# hv_relay_array.net
KiCad netlist of a schematic drawn in EAGLE
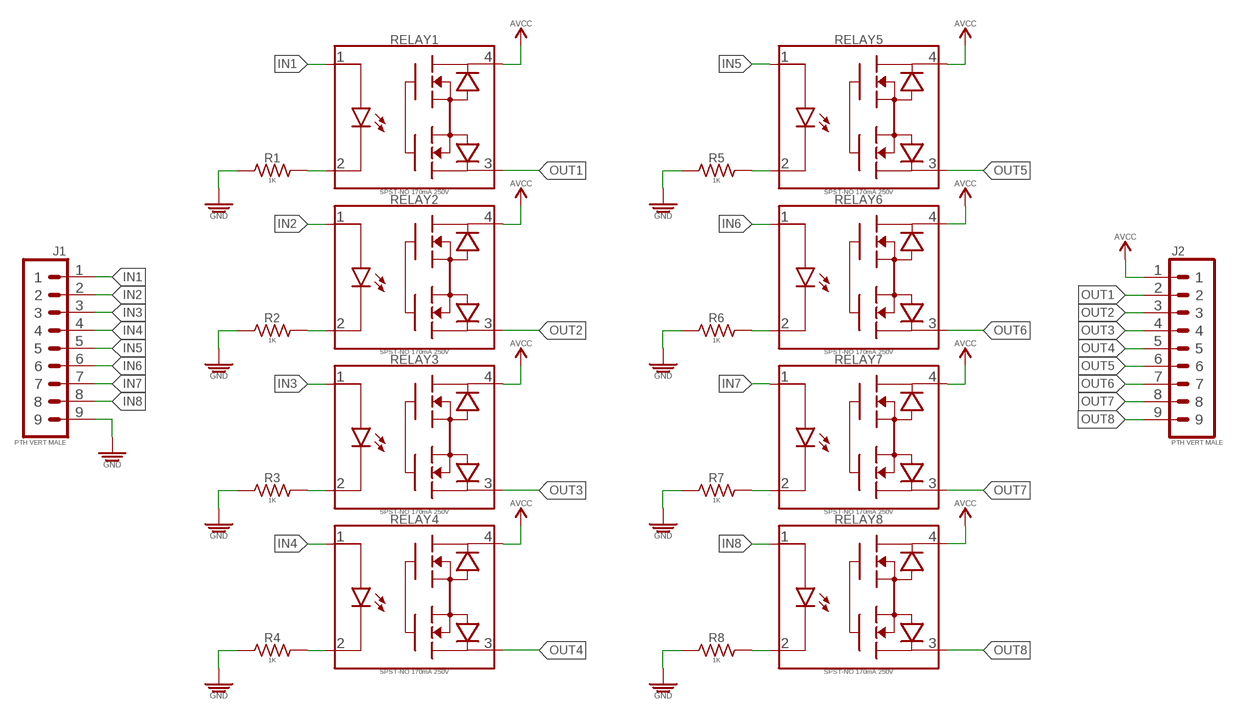
[diagram p0: schematic, sheet 1]

(export (version "E")
  (design (tool "Eeschema 10.0.6"))
  (components
    (comp (ref "J1")
      (value "PTH VERT MALE")
      (footprint "eagle-import:HDRV9W64P254_1X9_2286X254X838B")
      (fields (field (name "MFR") "Sullins Connector Solutions") (field (name "MPN") "PEC09SAAN"))
      (libsource (lib "eagle-import") (part "1X09_PTH_VERT_MALE_2.54MM"))
    )
    (comp (ref "J2")
      (value "PTH VERT MALE")
      (footprint "eagle-import:HDRV9W64P254_1X9_2286X254X838B")
      (fields (field (name "MFR") "Sullins Connector Solutions") (field (name "MPN") "PEC09SAAN"))
      (libsource (lib "eagle-import") (part "1X09_PTH_VERT_MALE_2.54MM"))
    )
    (comp (ref "R1")
      (value "1K")
      (footprint "eagle-import:RESC1005X35_SMD-0402")
      (fields (field (name "MFR") "Yageo") (field (name "MPN") "RC0402JR-071KL"))
      (libsource (lib "eagle-import") (part "1KΩ_SMD-0402_1/16W-5%"))
    )
    (comp (ref "R2")
      (value "1K")
      (footprint "eagle-import:RESC1005X35_SMD-0402")
      (fields (field (name "MFR") "Yageo") (field (name "MPN") "RC0402JR-071KL"))
      (libsource (lib "eagle-import") (part "1KΩ_SMD-0402_1/16W-5%"))
    )
    (comp (ref "R3")
      (value "1K")
      (footprint "eagle-import:RESC1005X35_SMD-0402")
      (fields (field (name "MFR") "Yageo") (field (name "MPN") "RC0402JR-071KL"))
      (libsource (lib "eagle-import") (part "1KΩ_SMD-0402_1/16W-5%"))
    )
    (comp (ref "R4")
      (value "1K")
      (footprint "eagle-import:RESC1005X35_SMD-0402")
      (fields (field (name "MFR") "Yageo") (field (name "MPN") "RC0402JR-071KL"))
      (libsource (lib "eagle-import") (part "1KΩ_SMD-0402_1/16W-5%"))
    )
    (comp (ref "R5")
      (value "1K")
      (footprint "eagle-import:RESC1005X35_SMD-0402")
      (fields (field (name "MFR") "Yageo") (field (name "MPN") "RC0402JR-071KL"))
      (libsource (lib "eagle-import") (part "1KΩ_SMD-0402_1/16W-5%"))
    )
    (comp (ref "R6")
      (value "1K")
      (footprint "eagle-import:RESC1005X35_SMD-0402")
      (fields (field (name "MFR") "Yageo") (field (name "MPN") "RC0402JR-071KL"))
      (libsource (lib "eagle-import") (part "1KΩ_SMD-0402_1/16W-5%"))
    )
    (comp (ref "R7")
      (value "1K")
      (footprint "eagle-import:RESC1005X35_SMD-0402")
      (fields (field (name "MFR") "Yageo") (field (name "MPN") "RC0402JR-071KL"))
      (libsource (lib "eagle-import") (part "1KΩ_SMD-0402_1/16W-5%"))
    )
    (comp (ref "R8")
      (value "1K")
      (footprint "eagle-import:RESC1005X35_SMD-0402")
      (fields (field (name "MFR") "Yageo") (field (name "MPN") "RC0402JR-071KL"))
      (libsource (lib "eagle-import") (part "1KΩ_SMD-0402_1/16W-5%"))
    )
    (comp (ref "RELAY1")
      (value "SPST-NO 170mA 250V")
      (footprint "eagle-import:SOP254P609X203-4")
      (fields (field (name "MFR") "IXYS Integrated Circuits Division") (field (name "MPN") "CPC1010N"))
      (libsource (lib "eagle-import") (part "RELAY_SOLID-STATE_SSR_170MA_250V_SPST-NO"))
    )
    (comp (ref "RELAY2")
      (value "SPST-NO 170mA 250V")
      (footprint "eagle-import:SOP254P609X203-4")
      (fields (field (name "MFR") "IXYS Integrated Circuits Division") (field (name "MPN") "CPC1010N"))
      (libsource (lib "eagle-import") (part "RELAY_SOLID-STATE_SSR_170MA_250V_SPST-NO"))
    )
    (comp (ref "RELAY3")
      (value "SPST-NO 170mA 250V")
      (footprint "eagle-import:SOP254P609X203-4")
      (fields (field (name "MFR") "IXYS Integrated Circuits Division") (field (name "MPN") "CPC1010N"))
      (libsource (lib "eagle-import") (part "RELAY_SOLID-STATE_SSR_170MA_250V_SPST-NO"))
    )
    (comp (ref "RELAY4")
      (value "SPST-NO 170mA 250V")
      (footprint "eagle-import:SOP254P609X203-4")
      (fields (field (name "MFR") "IXYS Integrated Circuits Division") (field (name "MPN") "CPC1010N"))
      (libsource (lib "eagle-import") (part "RELAY_SOLID-STATE_SSR_170MA_250V_SPST-NO"))
    )
    (comp (ref "RELAY5")
      (value "SPST-NO 170mA 250V")
      (footprint "eagle-import:SOP254P609X203-4")
      (fields (field (name "MFR") "IXYS Integrated Circuits Division") (field (name "MPN") "CPC1010N"))
      (libsource (lib "eagle-import") (part "RELAY_SOLID-STATE_SSR_170MA_250V_SPST-NO"))
    )
    (comp (ref "RELAY6")
      (value "SPST-NO 170mA 250V")
      (footprint "eagle-import:SOP254P609X203-4")
      (fields (field (name "MFR") "IXYS Integrated Circuits Division") (field (name "MPN") "CPC1010N"))
      (libsource (lib "eagle-import") (part "RELAY_SOLID-STATE_SSR_170MA_250V_SPST-NO"))
    )
    (comp (ref "RELAY7")
      (value "SPST-NO 170mA 250V")
      (footprint "eagle-import:SOP254P609X203-4")
      (fields (field (name "MFR") "IXYS Integrated Circuits Division") (field (name "MPN") "CPC1010N"))
      (libsource (lib "eagle-import") (part "RELAY_SOLID-STATE_SSR_170MA_250V_SPST-NO"))
    )
    (comp (ref "RELAY8")
      (value "SPST-NO 170mA 250V")
      (footprint "eagle-import:SOP254P609X203-4")
      (fields (field (name "MFR") "IXYS Integrated Circuits Division") (field (name "MPN") "CPC1010N"))
      (libsource (lib "eagle-import") (part "RELAY_SOLID-STATE_SSR_170MA_250V_SPST-NO"))
    )
  )
  (nets
    (net (code "1") (name "AVCC") (class "Default")
      (node (ref "J2") (pin "1") (pinfunction "1_1") (pintype "passive"))
      (node (ref "RELAY1") (pin "4") (pinfunction "4_4") (pintype "bidirectional"))
      (node (ref "RELAY2") (pin "4") (pinfunction "4_4") (pintype "bidirectional"))
      (node (ref "RELAY3") (pin "4") (pinfunction "4_4") (pintype "bidirectional"))
      (node (ref "RELAY4") (pin "4") (pinfunction "4_4") (pintype "bidirectional"))
      (node (ref "RELAY5") (pin "4") (pinfunction "4_4") (pintype "bidirectional"))
      (node (ref "RELAY6") (pin "4") (pinfunction "4_4") (pintype "bidirectional"))
      (node (ref "RELAY7") (pin "4") (pinfunction "4_4") (pintype "bidirectional"))
      (node (ref "RELAY8") (pin "4") (pinfunction "4_4") (pintype "bidirectional"))
    )
    (net (code "2") (name "GND") (class "Default")
      (node (ref "J1") (pin "9") (pinfunction "9_9") (pintype "passive"))
      (node (ref "R1") (pin "1") (pinfunction "1_1") (pintype "passive"))
      (node (ref "R2") (pin "1") (pinfunction "1_1") (pintype "passive"))
      (node (ref "R3") (pin "1") (pinfunction "1_1") (pintype "passive"))
      (node (ref "R4") (pin "1") (pinfunction "1_1") (pintype "passive"))
      (node (ref "R5") (pin "1") (pinfunction "1_1") (pintype "passive"))
      (node (ref "R6") (pin "1") (pinfunction "1_1") (pintype "passive"))
      (node (ref "R7") (pin "1") (pinfunction "1_1") (pintype "passive"))
      (node (ref "R8") (pin "1") (pinfunction "1_1") (pintype "passive"))
    )
    (net (code "3") (name "IN1") (class "Default")
      (node (ref "J1") (pin "1") (pinfunction "1_1") (pintype "passive"))
      (node (ref "RELAY1") (pin "1") (pinfunction "1_1") (pintype "bidirectional"))
    )
    (net (code "4") (name "IN2") (class "Default")
      (node (ref "J1") (pin "2") (pinfunction "2_2") (pintype "passive"))
      (node (ref "RELAY2") (pin "1") (pinfunction "1_1") (pintype "bidirectional"))
    )
    (net (code "5") (name "IN3") (class "Default")
      (node (ref "J1") (pin "3") (pinfunction "3_3") (pintype "passive"))
      (node (ref "RELAY3") (pin "1") (pinfunction "1_1") (pintype "bidirectional"))
    )
    (net (code "6") (name "IN4") (class "Default")
      (node (ref "J1") (pin "4") (pinfunction "4_4") (pintype "passive"))
      (node (ref "RELAY4") (pin "1") (pinfunction "1_1") (pintype "bidirectional"))
    )
    (net (code "7") (name "IN5") (class "Default")
      (node (ref "J1") (pin "5") (pinfunction "5_5") (pintype "passive"))
      (node (ref "RELAY5") (pin "1") (pinfunction "1_1") (pintype "bidirectional"))
    )
    (net (code "8") (name "IN6") (class "Default")
      (node (ref "J1") (pin "6") (pinfunction "6_6") (pintype "passive"))
      (node (ref "RELAY6") (pin "1") (pinfunction "1_1") (pintype "bidirectional"))
    )
    (net (code "9") (name "IN7") (class "Default")
      (node (ref "J1") (pin "7") (pinfunction "7_7") (pintype "passive"))
      (node (ref "RELAY7") (pin "1") (pinfunction "1_1") (pintype "bidirectional"))
    )
    (net (code "10") (name "IN8") (class "Default")
      (node (ref "J1") (pin "8") (pinfunction "8_8") (pintype "passive"))
      (node (ref "RELAY8") (pin "1") (pinfunction "1_1") (pintype "bidirectional"))
    )
    (net (code "11") (name "Net-(R1-Pad2)") (class "Default")
      (node (ref "R1") (pin "2") (pinfunction "2_2") (pintype "passive"))
      (node (ref "RELAY1") (pin "2") (pinfunction "2_2") (pintype "bidirectional"))
    )
    (net (code "12") (name "Net-(R2-Pad2)") (class "Default")
      (node (ref "R2") (pin "2") (pinfunction "2_2") (pintype "passive"))
      (node (ref "RELAY2") (pin "2") (pinfunction "2_2") (pintype "bidirectional"))
    )
    (net (code "13") (name "Net-(R3-Pad2)") (class "Default")
      (node (ref "R3") (pin "2") (pinfunction "2_2") (pintype "passive"))
      (node (ref "RELAY3") (pin "2") (pinfunction "2_2") (pintype "bidirectional"))
    )
    (net (code "14") (name "Net-(R4-Pad2)") (class "Default")
      (node (ref "R4") (pin "2") (pinfunction "2_2") (pintype "passive"))
      (node (ref "RELAY4") (pin "2") (pinfunction "2_2") (pintype "bidirectional"))
    )
    (net (code "15") (name "Net-(R5-Pad2)") (class "Default")
      (node (ref "R5") (pin "2") (pinfunction "2_2") (pintype "passive"))
      (node (ref "RELAY5") (pin "2") (pinfunction "2_2") (pintype "bidirectional"))
    )
    (net (code "16") (name "Net-(R6-Pad2)") (class "Default")
      (node (ref "R6") (pin "2") (pinfunction "2_2") (pintype "passive"))
      (node (ref "RELAY6") (pin "2") (pinfunction "2_2") (pintype "bidirectional"))
    )
    (net (code "17") (name "Net-(R7-Pad2)") (class "Default")
      (node (ref "R7") (pin "2") (pinfunction "2_2") (pintype "passive"))
      (node (ref "RELAY7") (pin "2") (pinfunction "2_2") (pintype "bidirectional"))
    )
    (net (code "18") (name "Net-(R8-Pad2)") (class "Default")
      (node (ref "R8") (pin "2") (pinfunction "2_2") (pintype "passive"))
      (node (ref "RELAY8") (pin "2") (pinfunction "2_2") (pintype "bidirectional"))
    )
    (net (code "19") (name "OUT1") (class "Default")
      (node (ref "J2") (pin "2") (pinfunction "2_2") (pintype "passive"))
      (node (ref "RELAY1") (pin "3") (pinfunction "3_3") (pintype "bidirectional"))
    )
    (net (code "20") (name "OUT2") (class "Default")
      (node (ref "J2") (pin "3") (pinfunction "3_3") (pintype "passive"))
      (node (ref "RELAY2") (pin "3") (pinfunction "3_3") (pintype "bidirectional"))
    )
    (net (code "21") (name "OUT3") (class "Default")
      (node (ref "J2") (pin "4") (pinfunction "4_4") (pintype "passive"))
      (node (ref "RELAY3") (pin "3") (pinfunction "3_3") (pintype "bidirectional"))
    )
    (net (code "22") (name "OUT4") (class "Default")
      (node (ref "J2") (pin "5") (pinfunction "5_5") (pintype "passive"))
      (node (ref "RELAY4") (pin "3") (pinfunction "3_3") (pintype "bidirectional"))
    )
    (net (code "23") (name "OUT5") (class "Default")
      (node (ref "J2") (pin "6") (pinfunction "6_6") (pintype "passive"))
      (node (ref "RELAY5") (pin "3") (pinfunction "3_3") (pintype "bidirectional"))
    )
    (net (code "24") (name "OUT6") (class "Default")
      (node (ref "J2") (pin "7") (pinfunction "7_7") (pintype "passive"))
      (node (ref "RELAY6") (pin "3") (pinfunction "3_3") (pintype "bidirectional"))
    )
    (net (code "25") (name "OUT7") (class "Default")
      (node (ref "J2") (pin "8") (pinfunction "8_8") (pintype "passive"))
      (node (ref "RELAY7") (pin "3") (pinfunction "3_3") (pintype "bidirectional"))
    )
    (net (code "26") (name "OUT8") (class "Default")
      (node (ref "J2") (pin "9") (pinfunction "9_9") (pintype "passive"))
      (node (ref "RELAY8") (pin "3") (pinfunction "3_3") (pintype "bidirectional"))
    )
  )
)
